# Booster_PA_OUT.net
KiCad netlist of a schematic drawn in Altium Designer
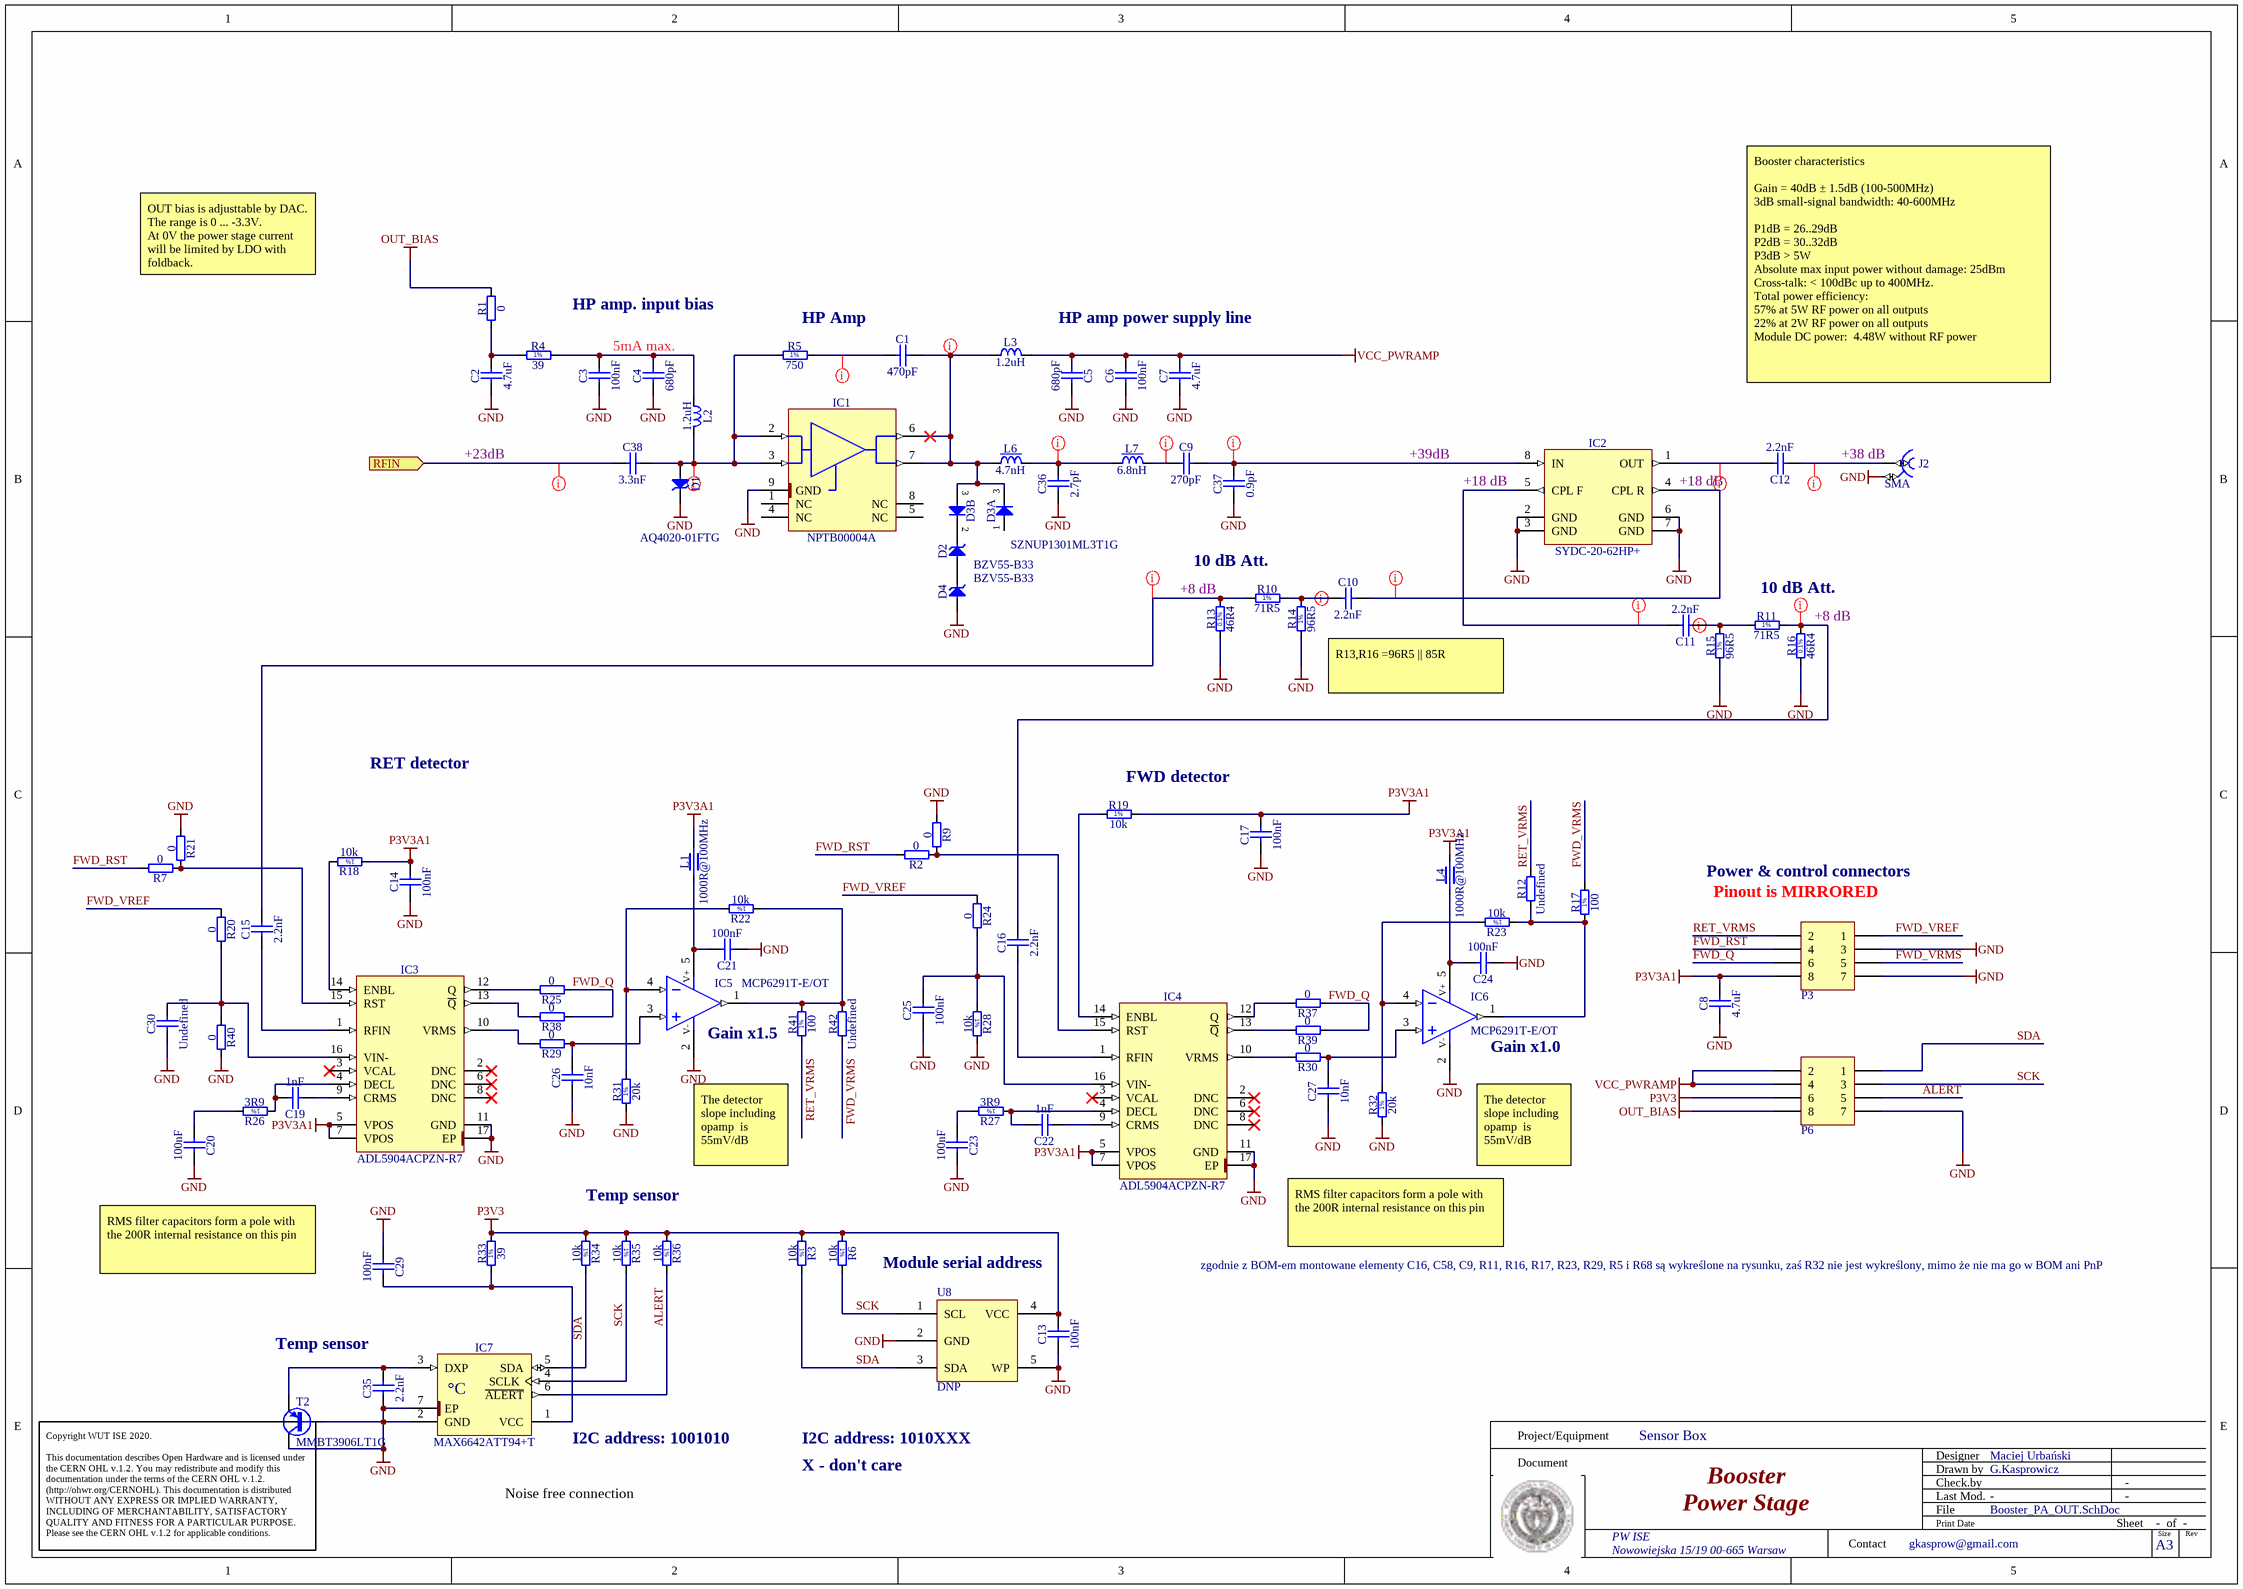
[diagram p0: Booster_PA_OUT.SchDoc]

(export (version "E")
  (design (tool "Eeschema 10.0.6"))
  (components
    (comp (ref "C1")
      (value "470pF")
      (footprint "CAPC1608X87N")
      (description "Non-polarised capacitor")
      (fields (field (name "PART NUMBER") "CC0603_470PF_50V_1%_NP0") (field (name "VOLTAGE") "50V"))
      (libsource (lib "Passives_RC") (part "CC0603_470PF_50V_1%_NP0"))
    )
    (comp (ref "C2")
      (value "4.7uF")
      (footprint "CAPC1709X95N")
      (description "Non-polarised capacitor")
      (fields
        (field (name "MANUFACTURER") "GENERIC")
        (field (name "MANUFACTURER PART NUMBER") "CC0603_4.7UF_16V_10%_X5R")
      )
      (libsource (lib "Capacitors") (part "Capacitor - non polarized"))
    )
    (comp (ref "C3")
      (value "100nF")
      (footprint "CAPC1005X55N")
      (description "Non-polarised capacitor")
      (fields
        (field (name "MANUFACTURER") "GENERIC")
        (field (name "MANUFACTURER PART NUMBER") "CC0402_100NF_50V_10%_X7R")
      )
      (libsource (lib "Capacitors") (part "Capacitor - non polarized"))
    )
    (comp (ref "C4")
      (value "680pF")
      (footprint "CAPC1608X87N")
      (description "Non-polarised capacitor")
      (fields
        (field (name "MANUFACTURER") "GENERIC")
        (field (name "MANUFACTURER PART NUMBER") "CC0603_680PF_50V_5%_NP0")
      )
      (libsource (lib "Capacitors") (part "Capacitor - non polarized"))
    )
    (comp (ref "C5")
      (value "680pF")
      (footprint "CAPC1608X87N")
      (description "Non-polarised capacitor")
      (fields
        (field (name "MANUFACTURER") "GENERIC")
        (field (name "MANUFACTURER PART NUMBER") "CC0603_680PF_50V_5%_NP0")
      )
      (libsource (lib "Capacitors") (part "Capacitor - non polarized"))
    )
    (comp (ref "C6")
      (value "100nF")
      (footprint "CAPC1005X55N")
      (description "Non-polarised capacitor")
      (fields
        (field (name "MANUFACTURER") "GENERIC")
        (field (name "MANUFACTURER PART NUMBER") "CC0402_100NF_50V_10%_X7R")
      )
      (libsource (lib "Capacitors") (part "Capacitor - non polarized"))
    )
    (comp (ref "C7")
      (value "4.7uF")
      (footprint "CAPC3225X270N")
      (description "Non-polarised capacitor")
      (fields (field (name "PART NUMBER") "CC1210_4.7UF_50V_10%_X7R") (field (name "VOLTAGE") "50V"))
      (libsource (lib "Capacitors") (part "Capacitor - non polarized"))
    )
    (comp (ref "C8")
      (value "4.7uF")
      (footprint "CAPC1709X95N")
      (description "Non-polarised capacitor")
      (fields
        (field (name "MANUFACTURER") "GENERIC")
        (field (name "MANUFACTURER PART NUMBER") "CC0603_4.7UF_16V_10%_X5R")
      )
      (libsource (lib "Capacitors") (part "Capacitor - non polarized"))
    )
    (comp (ref "C9")
      (value "270pF")
      (footprint "CAPC1608X87N")
      (description "Non-polarised capacitor")
      (fields (field (name "PART NUMBER") "CC0603_270PF_50V_1%_NP0") (field (name "VOLTAGE") "50V"))
      (libsource (lib "Passives_RC") (part "CC0603_270PF_50V_1%_NP0"))
    )
    (comp (ref "C10")
      (value "2.2nF")
      (footprint "CAPC1608X87N")
      (description "Non-polarised capacitor")
      (fields (field (name "PART NUMBER") "CC0603_2.2NF_50V_5%_C0G") (field (name "VOLTAGE") "50V"))
      (libsource (lib "Capacitors") (part "Capacitor - non polarized"))
    )
    (comp (ref "C11")
      (value "2.2nF")
      (footprint "CAPC1608X87N")
      (description "Non-polarised capacitor")
      (fields
        (field (name "MANUFACTURER") "GENERIC")
        (field (name "MANUFACTURER PART NUMBER") "CC0603_2.2NF_50V_5%_C0G")
      )
      (libsource (lib "Capacitors") (part "Capacitor - non polarized"))
    )
    (comp (ref "C12")
      (value "2.2nF")
      (footprint "CAPC1608X87N")
      (description "Non-polarised capacitor")
      (fields
        (field (name "MANUFACTURER") "GENERIC")
        (field (name "MANUFACTURER PART NUMBER") "CC0603_2.2NF_50V_5%_C0G")
      )
      (libsource (lib "Capacitors") (part "Capacitor - non polarized"))
    )
    (comp (ref "C13")
      (value "100nF")
      (footprint "CAPC1005X55N")
      (description "Non-polarised capacitor")
      (fields
        (field (name "MANUFACTURER") "GENERIC")
        (field (name "MANUFACTURER PART NUMBER") "CC0402_100NF_50V_10%_X7R")
      )
      (libsource (lib "Capacitors") (part "Capacitor - non polarized"))
    )
    (comp (ref "C14")
      (value "100nF")
      (footprint "CAPC1005X55N")
      (description "Non-polarised capacitor")
      (fields
        (field (name "MANUFACTURER") "GENERIC")
        (field (name "MANUFACTURER PART NUMBER") "CC0402_100NF_50V_10%_X7R")
      )
      (libsource (lib "Capacitors") (part "Capacitor - non polarized"))
    )
    (comp (ref "C15")
      (value "2.2nF")
      (footprint "CAPC1608X87N")
      (description "Non-polarised capacitor")
      (fields
        (field (name "MANUFACTURER") "GENERIC")
        (field (name "MANUFACTURER PART NUMBER") "CC0603_2.2NF_50V_5%_C0G")
      )
      (libsource (lib "Capacitors") (part "Capacitor - non polarized"))
    )
    (comp (ref "C16")
      (value "2.2nF")
      (footprint "CAPC1608X87N")
      (description "Non-polarised capacitor")
      (fields
        (field (name "MANUFACTURER") "GENERIC")
        (field (name "MANUFACTURER PART NUMBER") "CC0603_2.2NF_50V_5%_C0G")
      )
      (libsource (lib "Capacitors") (part "Capacitor - non polarized"))
    )
    (comp (ref "C17")
      (value "100nF")
      (footprint "CAPC1005X55N")
      (description "Non-polarised capacitor")
      (fields
        (field (name "MANUFACTURER") "GENERIC")
        (field (name "MANUFACTURER PART NUMBER") "CC0402_100NF_50V_10%_X7R")
      )
      (libsource (lib "Capacitors") (part "Capacitor - non polarized"))
    )
    (comp (ref "C19")
      (value "1nF")
      (footprint "CAPC1005X55N")
      (description "Non-polarised capacitor")
      (fields (field (name "PART NUMBER") "CC0402_1NF_50V_10%_X7R") (field (name "VOLTAGE") "50V"))
      (libsource (lib "Capacitors") (part "Capacitor - non polarized"))
    )
    (comp (ref "C20")
      (value "100nF")
      (footprint "CAPC1005X55N")
      (description "Non-polarised capacitor")
      (fields
        (field (name "MANUFACTURER") "GENERIC")
        (field (name "MANUFACTURER PART NUMBER") "CC0402_100NF_50V_10%_X7R")
      )
      (libsource (lib "Capacitors") (part "Capacitor - non polarized"))
    )
    (comp (ref "C21")
      (value "100nF")
      (footprint "CAPC1005X55N")
      (description "Non-polarised capacitor")
      (fields
        (field (name "MANUFACTURER") "GENERIC")
        (field (name "MANUFACTURER PART NUMBER") "CC0402_100NF_50V_10%_X7R")
      )
      (libsource (lib "Capacitors") (part "Capacitor - non polarized"))
    )
    (comp (ref "C22")
      (value "1nF")
      (footprint "CAPC1005X55N")
      (description "Non-polarised capacitor")
      (fields (field (name "PART NUMBER") "CC0402_1NF_50V_10%_X7R") (field (name "VOLTAGE") "50V"))
      (libsource (lib "Capacitors") (part "Capacitor - non polarized"))
    )
    (comp (ref "C23")
      (value "100nF")
      (footprint "CAPC1005X55N")
      (description "Non-polarised capacitor")
      (fields
        (field (name "MANUFACTURER") "GENERIC")
        (field (name "MANUFACTURER PART NUMBER") "CC0402_100NF_50V_10%_X7R")
      )
      (libsource (lib "Capacitors") (part "Capacitor - non polarized"))
    )
    (comp (ref "C24")
      (value "100nF")
      (footprint "CAPC1005X55N")
      (description "Non-polarised capacitor")
      (fields
        (field (name "MANUFACTURER") "GENERIC")
        (field (name "MANUFACTURER PART NUMBER") "CC0402_100NF_50V_10%_X7R")
      )
      (libsource (lib "Capacitors") (part "Capacitor - non polarized"))
    )
    (comp (ref "C25")
      (value "100nF")
      (footprint "CAPC1005X55N")
      (description "Non-polarised capacitor")
      (fields
        (field (name "MANUFACTURER") "GENERIC")
        (field (name "MANUFACTURER PART NUMBER") "CC0402_100NF_50V_10%_X7R")
      )
      (libsource (lib "Capacitors") (part "Capacitor - non polarized"))
    )
    (comp (ref "C26")
      (value "10nF")
      (footprint "CAPC1005X55N")
      (description "Non-polarised capacitor")
      (fields
        (field (name "MANUFACTURER") "GENERIC")
        (field (name "MANUFACTURER PART NUMBER") "CC0402_10NF_25V_10%_X7R")
      )
      (libsource (lib "Capacitors") (part "Capacitor - non polarized"))
    )
    (comp (ref "C27")
      (value "10nF")
      (footprint "CAPC1005X55N")
      (description "Non-polarised capacitor")
      (fields
        (field (name "MANUFACTURER") "GENERIC")
        (field (name "MANUFACTURER PART NUMBER") "CC0402_10NF_25V_10%_X7R")
      )
      (libsource (lib "Capacitors") (part "Capacitor - non polarized"))
    )
    (comp (ref "C29")
      (value "100nF")
      (footprint "CAPC1005X55N")
      (description "Non-polarised capacitor")
      (fields
        (field (name "MANUFACTURER") "GENERIC")
        (field (name "MANUFACTURER PART NUMBER") "CC0402_100NF_50V_10%_X7R")
      )
      (libsource (lib "Capacitors") (part "Capacitor - non polarized"))
    )
    (comp (ref "C30")
      (value "Undefined")
      (footprint "CAPC1608X90N")
      (description "Non-polarised capacitor")
      (fields (field (name "PART NUMBER") "CC0603_NO-VALUE"))
      (libsource (lib "Capacitors") (part "Capacitor - non polarized"))
    )
    (comp (ref "C35")
      (value "2.2nF")
      (footprint "CAPC1608X87N")
      (description "Non-polarised capacitor")
      (fields
        (field (name "MANUFACTURER") "GENERIC")
        (field (name "MANUFACTURER PART NUMBER") "CC0603_2.2NF_50V_5%_C0G")
      )
      (libsource (lib "Capacitors") (part "Capacitor - non polarized"))
    )
    (comp (ref "C36")
      (value "2.7pF")
      (footprint "CAPC1608X87N")
      (description "Non-polarised capacitor")
      (fields (field (name "PART NUMBER") "CC0603_2.7PF_50V_0.25PF_NP0") (field (name "VOLTAGE") "50V"))
      (libsource (lib "Capacitors") (part "Capacitor - non polarized"))
    )
    (comp (ref "C37")
      (value "0.9pF")
      (footprint "CAPC1608X87N")
      (description "Non-polarised capacitor")
      (fields (field (name "PART NUMBER") "CC0603_0.9PF_50V_0.05PF_NP0") (field (name "VOLTAGE") "50V"))
      (libsource (lib "Passives_RC") (part "CC0603_0.9PF_50V_0.05PF_NP0"))
    )
    (comp (ref "C38")
      (value "3.3nF")
      (footprint "CAPC1608X87N")
      (description "Non-polarised capacitor")
      (fields
        (field (name "MANUFACTURER") "GENERIC")
        (field (name "MANUFACTURER PART NUMBER") "CC0603_3.3NF_50V_5%_C0G")
      )
      (libsource (lib "Capacitors") (part "Capacitor - non polarized"))
    )
    (comp (ref "D1")
      (value "AQ4020-01FTG")
      (footprint "SOD2512X110N")
      (description "4V Transient Voltage Suppressor Diode (Uni-Directional)")
      (fields (field (name "VOLTAGE") "4V") (field (name "POWER") "735W"))
      (libsource (lib "Diodes") (part "D_TVS_AQ4020-01FTG"))
    )
    (comp (ref "D2")
      (value "BZV55-B33")
      (footprint "DIOMELF3515N")
      (description "Zener Diode")
      (fields (field (name "VOLTAGE") "33V") (field (name "POWER") "500mW"))
      (libsource (lib "ICs And Semiconductors") (part "Diode Zener"))
    )
    (comp (ref "D3")
      (value "SZNUP1301ML3T1G")
      (footprint "SOT95P240X110-3N")
      (description "Low Capacitance Diode Array for ESD Protection in a Single Data Line")
      (fields (field (name "VOLTAGE") "70V") (field (name "POWER") "215mA"))
      (libsource (lib "Diodes") (part "D_TVS_SZNUP1301ML3T1G"))
    )
    (comp (ref "D4")
      (value "BZV55-B33")
      (footprint "DIOMELF3515N")
      (description "Zener Diode")
      (fields (field (name "VOLTAGE") "33V") (field (name "POWER") "500mW"))
      (libsource (lib "ICs And Semiconductors") (part "Diode Zener"))
    )
    (comp (ref "IC1")
      (value "NPTB00004A")
      (footprint "SOIC127P610X167-9N-R245X335")
      (description "GaN Wideband Transistor 28V, 5W, DC - 6GHz")
      (fields (field (name "MANUFACTURER") "MACOM"))
      (libsource (lib "ICs And Semiconductors") (part "NPTB00004A"))
    )
    (comp (ref "IC2")
      (value "SYDC-20-62HP+")
      (footprint "MINI-CIRCUITS_AH202-1")
      (description "50Ohm, 10 to 540MHz, 25W, 20dB Bi-Directional Coupler")
      (fields (field (name "MANUFACTURER") "MINI-CIRCUITS"))
      (libsource (lib "ICs And Semiconductors") (part "SYDC-20-62HP+"))
    )
    (comp (ref "IC3")
      (value "ADL5904ACPZN-R7")
      (footprint "QFN50P300X300X80-17N-S175")
      (description "DC to 6 GHz, 45 dB TruPwr Detector With Envelope Threshold Detection")
      (fields (field (name "MANUFACTURER") "ANALOG DEVICES"))
      (libsource (lib "ICs And Semiconductors") (part "ADL5904"))
    )
    (comp (ref "IC4")
      (value "ADL5904ACPZN-R7")
      (footprint "QFN50P300X300X80-17N-S175")
      (description "DC to 6 GHz, 45 dB TruPwr Detector With Envelope Threshold Detection")
      (fields (field (name "MANUFACTURER") "ANALOG DEVICES"))
      (libsource (lib "ICs And Semiconductors") (part "ADL5904"))
    )
    (comp (ref "IC5")
      (value "MCP6291T-E/OT")
      (footprint "SOT95P270X145-5N")
      (description "Operational Amplifier")
      (fields (field (name "MANUFACTURER") "MICROCHIP TECHNOLOGY"))
      (libsource (lib "ICs And Semiconductors") (part "Operational Amplifier Type7"))
    )
    (comp (ref "IC6")
      (value "MCP6291T-E/OT")
      (footprint "SOT95P270X145-5N")
      (description "Operational Amplifier")
      (fields (field (name "MANUFACTURER") "MICROCHIP TECHNOLOGY"))
      (libsource (lib "ICs And Semiconductors") (part "Operational Amplifier Type7"))
    )
    (comp (ref "IC7")
      (value "MAX6642ATT94+T")
      (footprint "SON95P300X300X80-7N-R160X240")
      (description "±1°C, SMBus-Compatible Remote/Local Temperature Sensor with Overtemperature Alarm")
      (fields (field (name "MANUFACTURER") "MAXIM"))
      (libsource (lib "ICs And Semiconductors") (part "MAX6642ATT"))
    )
    (comp (ref "J2")
      (value "SMA")
      (footprint "MOLEX_73251-2120")
      (description "50 Ohm, SMA Edge Mount PCB, With Jam Nut And Lock Washer")
      (fields (field (name "PART NUMBER") "MOLEX_73251-2120") (field (name "MANUFACTURER") "MOLEX"))
      (libsource (lib "Connectors") (part "CON_SMA_RA_SMD_73251-2120"))
    )
    (comp (ref "L1")
      (value "1000R@100MHz")
      (footprint "INDC1608X95N")
      (fields
        (field (name "MANUFACTURER") "MURATA")
        (field (name "MANUFACTURER PART NUMBER") "BLM18HE102SN1")
        (field (name "PART NUMBER") "IND0603_MURATA_BLM18HE102SN1")
      )
      (libsource (lib "Inductors & Transformers") (part "Ferrite Bead"))
    )
    (comp (ref "L2")
      (value "1.2uH")
      (footprint "IND_TDK_ADL2012")
      (description "Inductor")
      (fields (field (name "PART NUMBER") "IND0805_TDK_ADL2012S-1R2M-T01") (field (name "POWER") "400mA"))
      (libsource (lib "Inductors_Transformers") (part "IND0805_TDK_ADL2012S-1R2M-T01"))
    )
    (comp (ref "L3")
      (value "1.2uH")
      (footprint "IND_TDK_ADL2012")
      (description "Inductor")
      (fields (field (name "PART NUMBER") "IND0805_TDK_ADL2012S-1R2M-T01") (field (name "POWER") "400mA"))
      (libsource (lib "") (part "IND0805_TDK_ADL2012S-1R2M-T01_1"))
    )
    (comp (ref "L4")
      (value "1000R@100MHz")
      (footprint "INDC1608X95N")
      (fields
        (field (name "MANUFACTURER") "MURATA")
        (field (name "MANUFACTURER PART NUMBER") "BLM18HE102SN1")
        (field (name "PART NUMBER") "IND0603_MURATA_BLM18HE102SN1")
      )
      (libsource (lib "Inductors & Transformers") (part "Ferrite Bead"))
    )
    (comp (ref "L6")
      (value "4.7nH")
      (footprint "IND_MURATA_LQW18AN_G8")
      (description "Inductor With Core")
      (fields
        (field (name "PART NUMBER") "IND0603_4.7NH_2%_MURATA_LQW18AN4N7G8Z")
        (field (name "POWER") "1.5A")
      )
      (libsource (lib "Inductors & Transformers") (part "Inductor With Magnetic core"))
    )
    (comp (ref "L7")
      (value "6.8nH")
      (footprint "IND_MURATA_LQW18AN_G8")
      (description "Inductor With Core")
      (fields
        (field (name "PART NUMBER") "IND0603_6.8NH_2%_MURATA_LQW18AN6N8G8Z")
        (field (name "POWER") "1.9A")
      )
      (libsource (lib "Inductors & Transformers") (part "Inductor With Magnetic core"))
    )
    (comp (ref "P3")
      (value "ZL264-8DG")
      (footprint "HDR2X4_SMD")
      (description "Header, 4-Pin, Dual Row")
      (libsource (lib "onyks") (part "HDR2X4"))
    )
    (comp (ref "P6")
      (value "ZL264-8DG")
      (footprint "HDR2X4_SMD")
      (description "Header, 4-Pin, Dual Row")
      (libsource (lib "onyks") (part "HDR2X4"))
    )
    (comp (ref "R1")
      (value "0")
      (footprint "RESC1005X40N")
      (description "Resistor")
      (fields
        (field (name "MANUFACTURER") "GENERIC")
        (field (name "MANUFACTURER PART NUMBER") "R0402_0R_JUMPER")
      )
      (libsource (lib "Resistors") (part "Resistor"))
    )
    (comp (ref "R2")
      (value "0")
      (footprint "RESC1005X40N")
      (description "Resistor")
      (fields
        (field (name "MANUFACTURER") "GENERIC")
        (field (name "MANUFACTURER PART NUMBER") "R0402_0R_JUMPER")
      )
      (libsource (lib "Resistors") (part "Resistor"))
    )
    (comp (ref "R3")
      (value "10k")
      (footprint "RESC1005X40N")
      (description "Resistor - 1%")
      (fields
        (field (name "MANUFACTURER") "GENERIC")
        (field (name "MANUFACTURER PART NUMBER") "R0402_10K_1%_0.0625W_100PPM")
      )
      (libsource (lib "Resistors") (part "Resistor - 1%"))
    )
    (comp (ref "R4")
      (value "39")
      (footprint "RESC1608X55N")
      (description "Resistor - 1%")
      (fields (field (name "PART NUMBER") "R0603_39R_1%_0.1W_100PPM") (field (name "POWER") "0.1W"))
      (libsource (lib "Resistors") (part "Resistor - 1%"))
    )
    (comp (ref "R5")
      (value "750")
      (footprint "RESC1608X55N")
      (description "Resistor - 1%")
      (fields (field (name "PART NUMBER") "R0603_750R_1%_0.1W_100PPM") (field (name "POWER") "0.1W"))
      (libsource (lib "Resistors") (part "Resistor - 1%"))
    )
    (comp (ref "R6")
      (value "10k")
      (footprint "RESC1005X40N")
      (description "Resistor - 1%")
      (fields
        (field (name "MANUFACTURER") "GENERIC")
        (field (name "MANUFACTURER PART NUMBER") "R0402_10K_1%_0.0625W_100PPM")
      )
      (libsource (lib "Resistors") (part "Resistor - 1%"))
    )
    (comp (ref "R7")
      (value "0")
      (footprint "RESC1005X40N")
      (description "Resistor")
      (fields
        (field (name "MANUFACTURER") "GENERIC")
        (field (name "MANUFACTURER PART NUMBER") "R0402_0R_JUMPER")
      )
      (libsource (lib "Resistors") (part "Resistor"))
    )
    (comp (ref "R9")
      (value "0")
      (footprint "RESC1005X40N")
      (description "Resistor")
      (fields
        (field (name "MANUFACTURER") "GENERIC")
        (field (name "MANUFACTURER PART NUMBER") "R0402_0R_JUMPER")
      )
      (libsource (lib "Resistors") (part "Resistor"))
    )
    (comp (ref "R10")
      (value "71R5")
      (footprint "RESC1608X55N")
      (description "Resistor - 1%")
      (fields (field (name "PART NUMBER") "R0603_71R5_1%_0.1W_100PPM") (field (name "POWER") "0.1W"))
      (libsource (lib "Resistors") (part "Resistor - 1%"))
    )
    (comp (ref "R11")
      (value "71R5")
      (footprint "RESC1608X55N")
      (description "Resistor - 1%")
      (fields (field (name "PART NUMBER") "R0603_71R5_1%_0.1W_100PPM") (field (name "POWER") "0.1W"))
      (libsource (lib "Resistors") (part "Resistor - 1%"))
    )
    (comp (ref "R12")
      (value "Undefined")
      (footprint "RESC1608X55N")
      (description "Resistor")
      (fields (field (name "MANUFACTURER PART NUMBER") "R0603_NO-VALUE"))
      (libsource (lib "Resistors") (part "Resistor"))
    )
    (comp (ref "R13")
      (value "46R4")
      (footprint "RESC1608X55N")
      (description "Resistor - 0.1%")
      (fields (field (name "PART NUMBER") "R0603_46R4_0.1%_0.063W_10PPM") (field (name "POWER") "0.063W"))
      (libsource (lib "Resistors") (part "Resistor - 0.1%"))
    )
    (comp (ref "R14")
      (value "96R5")
      (footprint "RESC1608X55N")
      (description "Resistor - 0.5%")
      (fields (field (name "PART NUMBER") "R0603_96R5_0.5%_0.1W_50PPM") (field (name "POWER") "0.1W"))
      (libsource (lib "Passives_RC") (part "R0603_96R5_0.5%_0.1W_50PPM"))
    )
    (comp (ref "R15")
      (value "96R5")
      (footprint "RESC1608X55N")
      (description "Resistor - 0.5%")
      (fields (field (name "PART NUMBER") "R0603_96R5_0.5%_0.1W_50PPM") (field (name "POWER") "0.1W"))
      (libsource (lib "Passives_RC") (part "R0603_96R5_0.5%_0.1W_50PPM"))
    )
    (comp (ref "R16")
      (value "46R4")
      (footprint "RESC1608X55N")
      (description "Resistor - 0.1%")
      (fields (field (name "PART NUMBER") "R0603_46R4_0.1%_0.063W_10PPM") (field (name "POWER") "0.063W"))
      (libsource (lib "Resistors") (part "Resistor - 0.1%"))
    )
    (comp (ref "R17")
      (value "100")
      (footprint "RESC1608X55N")
      (description "Resistor - 1%")
      (fields
        (field (name "MANUFACTURER") "GENERIC")
        (field (name "MANUFACTURER PART NUMBER") "R0603_100R_1%_0.1W_100PPM")
      )
      (libsource (lib "Resistors") (part "Resistor - 1%"))
    )
    (comp (ref "R18")
      (value "10k")
      (footprint "RESC1005X40N")
      (description "Resistor - 1%")
      (fields
        (field (name "MANUFACTURER") "GENERIC")
        (field (name "MANUFACTURER PART NUMBER") "R0402_10K_1%_0.0625W_100PPM")
      )
      (libsource (lib "Resistors") (part "Resistor - 1%"))
    )
    (comp (ref "R19")
      (value "10k")
      (footprint "RESC1005X40N")
      (description "Resistor - 1%")
      (fields (field (name "PART NUMBER") "R0402_10K_1%_0.0625W_100PPM") (field (name "POWER") "0.0625W"))
      (libsource (lib "Resistors") (part "Resistor - 1%"))
    )
    (comp (ref "R20")
      (value "0")
      (footprint "RESC1005X40N")
      (description "Resistor")
      (fields
        (field (name "MANUFACTURER") "GENERIC")
        (field (name "MANUFACTURER PART NUMBER") "R0402_0R_JUMPER")
      )
      (libsource (lib "Resistors") (part "Resistor"))
    )
    (comp (ref "R21")
      (value "0")
      (footprint "RESC1005X40N")
      (description "Resistor")
      (fields
        (field (name "MANUFACTURER") "GENERIC")
        (field (name "MANUFACTURER PART NUMBER") "R0402_0R_JUMPER")
      )
      (libsource (lib "Resistors") (part "Resistor"))
    )
    (comp (ref "R22")
      (value "10k")
      (footprint "RESC1005X40N")
      (description "Resistor - 1%")
      (fields
        (field (name "MANUFACTURER") "GENERIC")
        (field (name "MANUFACTURER PART NUMBER") "R0402_10K_1%_0.0625W_100PPM")
      )
      (libsource (lib "Resistors") (part "Resistor - 1%"))
    )
    (comp (ref "R23")
      (value "10k")
      (footprint "RESC1005X40N")
      (description "Resistor - 1%")
      (fields
        (field (name "MANUFACTURER") "GENERIC")
        (field (name "MANUFACTURER PART NUMBER") "R0402_10K_1%_0.0625W_100PPM")
      )
      (libsource (lib "Resistors") (part "Resistor - 1%"))
    )
    (comp (ref "R24")
      (value "0")
      (footprint "RESC1005X40N")
      (description "Resistor")
      (fields
        (field (name "MANUFACTURER") "GENERIC")
        (field (name "MANUFACTURER PART NUMBER") "R0402_0R_JUMPER")
      )
      (libsource (lib "Resistors") (part "Resistor"))
    )
    (comp (ref "R25")
      (value "0")
      (footprint "RESC1005X40N")
      (description "Resistor")
      (fields
        (field (name "MANUFACTURER") "GENERIC")
        (field (name "MANUFACTURER PART NUMBER") "R0402_0R_JUMPER")
      )
      (libsource (lib "Resistors") (part "Resistor"))
    )
    (comp (ref "R26")
      (value "3R9")
      (footprint "RESC1005X40N")
      (description "Resistor - 1%")
      (fields (field (name "PART NUMBER") "R0402_3R9_1%_0.0625W_200PPM") (field (name "POWER") "0.0625W"))
      (libsource (lib "Resistors") (part "Resistor - 1%"))
    )
    (comp (ref "R27")
      (value "3R9")
      (footprint "RESC1005X40N")
      (description "Resistor - 1%")
      (fields (field (name "PART NUMBER") "R0402_3R9_1%_0.0625W_200PPM") (field (name "POWER") "0.0625W"))
      (libsource (lib "Resistors") (part "Resistor - 1%"))
    )
    (comp (ref "R28")
      (value "10k")
      (footprint "RESC1005X40N")
      (description "Resistor - 1%")
      (fields
        (field (name "MANUFACTURER") "GENERIC")
        (field (name "MANUFACTURER PART NUMBER") "R0402_10K_1%_0.0625W_100PPM")
      )
      (libsource (lib "Resistors") (part "Resistor - 1%"))
    )
    (comp (ref "R29")
      (value "0")
      (footprint "RESC1005X40N")
      (description "Resistor")
      (fields
        (field (name "MANUFACTURER") "GENERIC")
        (field (name "MANUFACTURER PART NUMBER") "R0402_0R_JUMPER")
      )
      (libsource (lib "Resistors") (part "Resistor"))
    )
    (comp (ref "R30")
      (value "0")
      (footprint "RESC1005X40N")
      (description "Resistor")
      (fields
        (field (name "MANUFACTURER") "GENERIC")
        (field (name "MANUFACTURER PART NUMBER") "R0402_0R_JUMPER")
      )
      (libsource (lib "Resistors") (part "Resistor"))
    )
    (comp (ref "R31")
      (value "20k")
      (footprint "RESC1608X55N")
      (description "Resistor - 1%")
      (fields (field (name "PART NUMBER") "R0603_20K_1%_0.1W_100PPM") (field (name "POWER") "0.1W"))
      (libsource (lib "Resistors") (part "Resistor - 1%"))
    )
    (comp (ref "R32")
      (value "20k")
      (footprint "RESC1608X55N")
      (description "Resistor - 1%")
      (fields (field (name "PART NUMBER") "R0603_20K_1%_0.1W_100PPM") (field (name "POWER") "0.1W"))
      (libsource (lib "Resistors") (part "Resistor - 1%"))
    )
    (comp (ref "R33")
      (value "39")
      (footprint "RESC1608X55N")
      (description "Resistor - 1%")
      (fields (field (name "PART NUMBER") "R0603_39R_1%_0.1W_100PPM") (field (name "POWER") "0.1W"))
      (libsource (lib "Resistors") (part "Resistor - 1%"))
    )
    (comp (ref "R34")
      (value "10k")
      (footprint "RESC1005X40N")
      (description "Resistor - 1%")
      (fields
        (field (name "MANUFACTURER") "GENERIC")
        (field (name "MANUFACTURER PART NUMBER") "R0402_10K_1%_0.0625W_100PPM")
      )
      (libsource (lib "Resistors") (part "Resistor - 1%"))
    )
    (comp (ref "R35")
      (value "10k")
      (footprint "RESC1005X40N")
      (description "Resistor - 1%")
      (fields
        (field (name "MANUFACTURER") "GENERIC")
        (field (name "MANUFACTURER PART NUMBER") "R0402_10K_1%_0.0625W_100PPM")
      )
      (libsource (lib "Resistors") (part "Resistor - 1%"))
    )
    (comp (ref "R36")
      (value "10k")
      (footprint "RESC1005X40N")
      (description "Resistor - 1%")
      (fields
        (field (name "MANUFACTURER") "GENERIC")
        (field (name "MANUFACTURER PART NUMBER") "R0402_10K_1%_0.0625W_100PPM")
      )
      (libsource (lib "Resistors") (part "Resistor - 1%"))
    )
    (comp (ref "R37")
      (value "0")
      (footprint "RESC1005X40N")
      (description "Resistor")
      (fields
        (field (name "MANUFACTURER") "GENERIC")
        (field (name "MANUFACTURER PART NUMBER") "R0402_0R_JUMPER")
      )
      (libsource (lib "Resistors") (part "Resistor"))
    )
    (comp (ref "R38")
      (value "0")
      (footprint "RESC1005X40N")
      (description "Resistor")
      (fields
        (field (name "MANUFACTURER") "GENERIC")
        (field (name "MANUFACTURER PART NUMBER") "R0402_0R_JUMPER")
      )
      (libsource (lib "Resistors") (part "Resistor"))
    )
    (comp (ref "R39")
      (value "0")
      (footprint "RESC1005X40N")
      (description "Resistor")
      (fields
        (field (name "MANUFACTURER") "GENERIC")
        (field (name "MANUFACTURER PART NUMBER") "R0402_0R_JUMPER")
      )
      (libsource (lib "Resistors") (part "Resistor"))
    )
    (comp (ref "R40")
      (value "0")
      (footprint "RESC1005X40N")
      (description "Resistor")
      (fields
        (field (name "MANUFACTURER") "GENERIC")
        (field (name "MANUFACTURER PART NUMBER") "R0402_0R_JUMPER")
      )
      (libsource (lib "Resistors") (part "Resistor"))
    )
    (comp (ref "R41")
      (value "100")
      (footprint "RESC1608X55N")
      (description "Resistor - 1%")
      (fields
        (field (name "MANUFACTURER") "GENERIC")
        (field (name "MANUFACTURER PART NUMBER") "R0603_100R_1%_0.1W_100PPM")
      )
      (libsource (lib "Resistors") (part "Resistor - 1%"))
    )
    (comp (ref "R42")
      (value "Undefined")
      (footprint "RESC1608X55N")
      (description "Resistor")
      (fields (field (name "MANUFACTURER PART NUMBER") "R0603_NO-VALUE"))
      (libsource (lib "Resistors") (part "Resistor"))
    )
    (comp (ref "T2")
      (value "MMBT3906LT1G")
      (footprint "SOT95P240X110-3N")
      (description "PNP Transistor")
      (fields (field (name "MANUFACTURER") "ON SEMICONDUCTOR"))
      (libsource (lib "ICs And Semiconductors") (part "PNP B1 E2 C3"))
    )
    (comp (ref "U8")
      (value "DNP")
      (footprint "SOT23-5_N")
      (description "1K I2  C™ Serial EEPROM with Half-Array Write-Protect")
      (fields (field (name "MANUFACTURER") "Microchip"))
      (libsource (lib "uklady_cyfrowe") (part "24AA01H"))
    )
  )
  (nets
    (net (code "1") (name "/ALERT") (class "Default")
      (node (ref "IC7") (pin "6") (pinfunction "~{ALERT}_6") (pintype "output"))
      (node (ref "P6") (pin "5") (pinfunction "5_5") (pintype "passive"))
      (node (ref "R36") (pin "2") (pinfunction "2_2") (pintype "passive"))
    )
    (net (code "2") (name "/FWD_Q") (class "Default")
      (node (ref "P3") (pin "6") (pinfunction "6_6") (pintype "passive"))
      (node (ref "R25") (pin "1") (pinfunction "1_1") (pintype "passive"))
      (node (ref "R37") (pin "1") (pinfunction "1_1") (pintype "passive"))
      (node (ref "R38") (pin "1") (pinfunction "1_1") (pintype "passive"))
      (node (ref "R39") (pin "1") (pinfunction "1_1") (pintype "passive"))
    )
    (net (code "3") (name "/FWD_RST") (class "Default")
      (node (ref "P3") (pin "4") (pinfunction "4_4") (pintype "passive"))
      (node (ref "R2") (pin "2") (pinfunction "2_2") (pintype "passive"))
      (node (ref "R7") (pin "2") (pinfunction "2_2") (pintype "passive"))
    )
    (net (code "4") (name "/FWD_VREF") (class "Default")
      (node (ref "P3") (pin "1") (pinfunction "1_1") (pintype "passive"))
      (node (ref "R20") (pin "1") (pinfunction "1_1") (pintype "passive"))
      (node (ref "R24") (pin "1") (pinfunction "1_1") (pintype "passive"))
    )
    (net (code "5") (name "/FWD_VRMS") (class "Default")
      (node (ref "P3") (pin "5") (pinfunction "5_5") (pintype "passive"))
      (node (ref "R17") (pin "2") (pinfunction "2_2") (pintype "passive"))
      (node (ref "R42") (pin "1") (pinfunction "1_1") (pintype "passive"))
    )
    (net (code "6") (name "/RET_VRMS") (class "Default")
      (node (ref "P3") (pin "2") (pinfunction "2_2") (pintype "passive"))
      (node (ref "R12") (pin "2") (pinfunction "2_2") (pintype "passive"))
      (node (ref "R41") (pin "1") (pinfunction "1_1") (pintype "passive"))
    )
    (net (code "7") (name "/RFIN") (class "Default")
      (node (ref "C38") (pin "2") (pinfunction "2_2") (pintype "passive"))
    )
    (net (code "8") (name "/SCK") (class "Default")
      (node (ref "IC7") (pin "4") (pinfunction "SCLK_4") (pintype "input"))
      (node (ref "P6") (pin "3") (pinfunction "3_3") (pintype "passive"))
      (node (ref "R35") (pin "2") (pinfunction "2_2") (pintype "passive"))
      (node (ref "R6") (pin "2") (pinfunction "2_2") (pintype "passive"))
      (node (ref "U8") (pin "1") (pinfunction "SCL_1") (pintype "passive"))
    )
    (net (code "9") (name "/SDA") (class "Default")
      (node (ref "IC7") (pin "5") (pinfunction "SDA_5") (pintype "bidirectional"))
      (node (ref "P6") (pin "1") (pinfunction "1_1") (pintype "passive"))
      (node (ref "R3") (pin "2") (pinfunction "2_2") (pintype "passive"))
      (node (ref "R34") (pin "2") (pinfunction "2_2") (pintype "passive"))
      (node (ref "U8") (pin "3") (pinfunction "SDA_3") (pintype "passive"))
    )
    (net (code "10") (name "GND") (class "Default")
      (node (ref "C13") (pin "1") (pinfunction "1_1") (pintype "passive"))
      (node (ref "C14") (pin "1") (pinfunction "1_1") (pintype "passive"))
      (node (ref "C17") (pin "1") (pinfunction "1_1") (pintype "passive"))
      (node (ref "C2") (pin "1") (pinfunction "1_1") (pintype "passive"))
      (node (ref "C20") (pin "2") (pinfunction "2_2") (pintype "passive"))
      (node (ref "C21") (pin "1") (pinfunction "1_1") (pintype "passive"))
      (node (ref "C23") (pin "2") (pinfunction "2_2") (pintype "passive"))
      (node (ref "C24") (pin "1") (pinfunction "1_1") (pintype "passive"))
      (node (ref "C25") (pin "1") (pinfunction "1_1") (pintype "passive"))
      (node (ref "C26") (pin "1") (pinfunction "1_1") (pintype "passive"))
      (node (ref "C27") (pin "1") (pinfunction "1_1") (pintype "passive"))
      (node (ref "C29") (pin "1") (pinfunction "1_1") (pintype "passive"))
      (node (ref "C3") (pin "1") (pinfunction "1_1") (pintype "passive"))
      (node (ref "C30") (pin "1") (pinfunction "1_1") (pintype "passive"))
      (node (ref "C35") (pin "1") (pinfunction "1_1") (pintype "passive"))
      (node (ref "C36") (pin "1") (pinfunction "1_1") (pintype "passive"))
      (node (ref "C37") (pin "1") (pinfunction "1_1") (pintype "passive"))
      (node (ref "C4") (pin "1") (pinfunction "1_1") (pintype "passive"))
      (node (ref "C5") (pin "1") (pinfunction "1_1") (pintype "passive"))
      (node (ref "C6") (pin "1") (pinfunction "1_1") (pintype "passive"))
      (node (ref "C7") (pin "1") (pinfunction "1_1") (pintype "passive"))
      (node (ref "C8") (pin "1") (pinfunction "1_1") (pintype "passive"))
      (node (ref "D1") (pin "1") (pinfunction "C_1") (pintype "passive"))
      (node (ref "D4") (pin "2") (pinfunction "A_2") (pintype "passive"))
      (node (ref "IC1") (pin "9") (pinfunction "GND_9") (pintype "power_in"))
      (node (ref "IC2") (pin "2") (pinfunction "GND_2") (pintype "power_in"))
      (node (ref "IC2") (pin "3") (pinfunction "GND_3") (pintype "power_in"))
      (node (ref "IC2") (pin "6") (pinfunction "GND_6") (pintype "power_in"))
      (node (ref "IC2") (pin "7") (pinfunction "GND_7") (pintype "power_in"))
      (node (ref "IC3") (pin "11") (pinfunction "GND_11") (pintype "power_in"))
      (node (ref "IC3") (pin "17") (pinfunction "EP_17") (pintype "power_in"))
      (node (ref "IC4") (pin "11") (pinfunction "GND_11") (pintype "power_in"))
      (node (ref "IC4") (pin "17") (pinfunction "EP_17") (pintype "power_in"))
      (node (ref "IC5") (pin "2") (pinfunction "V-_2") (pintype "power_in"))
      (node (ref "IC6") (pin "2") (pinfunction "V-_2") (pintype "power_in"))
      (node (ref "IC7") (pin "2") (pinfunction "GND_2") (pintype "power_in"))
      (node (ref "IC7") (pin "7") (pinfunction "EP_7") (pintype "power_in"))
      (node (ref "J2") (pin "2") (pinfunction "2_2") (pintype "bidirectional"))
      (node (ref "P3") (pin "3") (pinfunction "3_3") (pintype "passive"))
      (node (ref "P3") (pin "7") (pinfunction "7_7") (pintype "passive"))
      (node (ref "P6") (pin "7") (pinfunction "7_7") (pintype "passive"))
      (node (ref "R13") (pin "1") (pinfunction "1_1") (pintype "passive"))
      (node (ref "R14") (pin "1") (pinfunction "1_1") (pintype "passive"))
      (node (ref "R15") (pin "1") (pinfunction "1_1") (pintype "passive"))
      (node (ref "R16") (pin "1") (pinfunction "1_1") (pintype "passive"))
      (node (ref "R21") (pin "1") (pinfunction "1_1") (pintype "passive"))
      (node (ref "R28") (pin "2") (pinfunction "2_2") (pintype "passive"))
      (node (ref "R31") (pin "1") (pinfunction "1_1") (pintype "passive"))
      (node (ref "R32") (pin "1") (pinfunction "1_1") (pintype "passive"))
      (node (ref "R40") (pin "2") (pinfunction "2_2") (pintype "passive"))
      (node (ref "R9") (pin "1") (pinfunction "1_1") (pintype "passive"))
      (node (ref "T2") (pin "1") (pinfunction "B_1") (pintype "passive"))
      (node (ref "T2") (pin "3") (pinfunction "C_3") (pintype "passive"))
      (node (ref "U8") (pin "2") (pinfunction "GND_2") (pintype "passive"))
      (node (ref "U8") (pin "5") (pinfunction "WP_5") (pintype "passive"))
    )
    (net (code "11") (name "Net-(C1-Pad1)") (class "Default")
      (node (ref "C1") (pin "1") (pinfunction "1_1") (pintype "passive"))
      (node (ref "R5") (pin "2") (pinfunction "2_2") (pintype "passive"))
    )
    (net (code "12") (name "Net-(C2-Pad2)") (class "Default")
      (node (ref "C2") (pin "2") (pinfunction "2_2") (pintype "passive"))
      (node (ref "R1") (pin "1") (pinfunction "1_1") (pintype "passive"))
      (node (ref "R4") (pin "1") (pinfunction "1_1") (pintype "passive"))
    )
    (net (code "13") (name "Net-(C3-Pad2)") (class "Default")
      (node (ref "C3") (pin "2") (pinfunction "2_2") (pintype "passive"))
      (node (ref "C4") (pin "2") (pinfunction "2_2") (pintype "passive"))
      (node (ref "L2") (pin "1") (pinfunction "1_1") (pintype "passive"))
      (node (ref "R4") (pin "2") (pinfunction "2_2") (pintype "passive"))
    )
    (net (code "14") (name "Net-(C9-Pad1)") (class "Default")
      (node (ref "C9") (pin "1") (pinfunction "1_1") (pintype "passive"))
      (node (ref "L7") (pin "2") (pinfunction "2_2") (pintype "passive"))
    )
    (net (code "15") (name "Net-(C10-Pad1)") (class "Default")
      (node (ref "C10") (pin "1") (pinfunction "1_1") (pintype "passive"))
      (node (ref "R10") (pin "2") (pinfunction "2_2") (pintype "passive"))
      (node (ref "R14") (pin "2") (pinfunction "2_2") (pintype "passive"))
    )
    (net (code "16") (name "Net-(C11-Pad1)") (class "Default")
      (node (ref "C11") (pin "1") (pinfunction "1_1") (pintype "passive"))
      (node (ref "R11") (pin "1") (pinfunction "1_1") (pintype "passive"))
      (node (ref "R15") (pin "2") (pinfunction "2_2") (pintype "passive"))
    )
    (net (code "17") (name "Net-(C12-Pad1)") (class "Default")
      (node (ref "C12") (pin "1") (pinfunction "1_1") (pintype "passive"))
      (node (ref "J2") (pin "1") (pinfunction "1_1") (pintype "bidirectional"))
    )
    (net (code "18") (name "Net-(C15-Pad2)") (class "Default")
      (node (ref "C15") (pin "2") (pinfunction "2_2") (pintype "passive"))
      (node (ref "R10") (pin "1") (pinfunction "1_1") (pintype "passive"))
      (node (ref "R13") (pin "2") (pinfunction "2_2") (pintype "passive"))
    )
    (net (code "19") (name "Net-(C16-Pad2)") (class "Default")
      (node (ref "C16") (pin "2") (pinfunction "2_2") (pintype "passive"))
      (node (ref "R11") (pin "2") (pinfunction "2_2") (pintype "passive"))
      (node (ref "R16") (pin "2") (pinfunction "2_2") (pintype "passive"))
    )
    (net (code "20") (name "Net-(C20-Pad1)") (class "Default")
      (node (ref "C20") (pin "1") (pinfunction "1_1") (pintype "passive"))
      (node (ref "R26") (pin "2") (pinfunction "2_2") (pintype "passive"))
    )
    (net (code "21") (name "Net-(C23-Pad1)") (class "Default")
      (node (ref "C23") (pin "1") (pinfunction "1_1") (pintype "passive"))
      (node (ref "R27") (pin "2") (pinfunction "2_2") (pintype "passive"))
    )
    (net (code "22") (name "Net-(C36-Pad2)") (class "Default")
      (node (ref "C36") (pin "2") (pinfunction "2_2") (pintype "passive"))
      (node (ref "L6") (pin "2") (pinfunction "2_2") (pintype "passive"))
      (node (ref "L7") (pin "1") (pinfunction "1_1") (pintype "passive"))
    )
    (net (code "23") (name "Net-(D1-A)") (class "Default")
      (node (ref "C38") (pin "1") (pinfunction "1_1") (pintype "passive"))
      (node (ref "D1") (pin "2") (pinfunction "A_2") (pintype "passive"))
      (node (ref "IC1") (pin "2") (pinfunction "RF_IN_2") (pintype "input"))
      (node (ref "IC1") (pin "3") (pinfunction "RF_IN_3") (pintype "input"))
      (node (ref "L2") (pin "2") (pinfunction "2_2") (pintype "passive"))
      (node (ref "R5") (pin "1") (pinfunction "1_1") (pintype "passive"))
    )
    (net (code "24") (name "Net-(D2-A)") (class "Default")
      (node (ref "D2") (pin "2") (pinfunction "A_2") (pintype "passive"))
      (node (ref "D4") (pin "1") (pinfunction "C_1") (pintype "passive"))
    )
    (net (code "25") (name "Net-(D2-C)") (class "Default")
      (node (ref "D2") (pin "1") (pinfunction "C_1") (pintype "passive"))
      (node (ref "D3") (pin "2") (pinfunction "C_2") (pintype "passive"))
    )
    (net (code "26") (name "Net-(D3A-COMAC)") (class "Default")
      (node (ref "C1") (pin "2") (pinfunction "2_2") (pintype "passive"))
      (node (ref "D3") (pin "3") (pinfunction "COMAC_3") (pintype "passive"))
      (node (ref "IC1") (pin "6") (pinfunction "RF_OUT_6") (pintype "output"))
      (node (ref "IC1") (pin "7") (pinfunction "RF_OUT_7") (pintype "output"))
      (node (ref "L3") (pin "1") (pinfunction "1_1") (pintype "passive"))
      (node (ref "L6") (pin "1") (pinfunction "1_1") (pintype "passive"))
    )
    (net (code "27") (name "Net-(IC2-CPL_F)") (class "Default")
      (node (ref "C11") (pin "2") (pinfunction "2_2") (pintype "passive"))
      (node (ref "IC2") (pin "5") (pinfunction "CPL_F_5") (pintype "output"))
    )
    (net (code "28") (name "Net-(IC2-CPL_R)") (class "Default")
      (node (ref "C10") (pin "2") (pinfunction "2_2") (pintype "passive"))
      (node (ref "IC2") (pin "4") (pinfunction "CPL_R_4") (pintype "output"))
    )
    (net (code "29") (name "Net-(IC2-IN)") (class "Default")
      (node (ref "C37") (pin "2") (pinfunction "2_2") (pintype "passive"))
      (node (ref "C9") (pin "2") (pinfunction "2_2") (pintype "passive"))
      (node (ref "IC2") (pin "8") (pinfunction "IN_8") (pintype "input"))
    )
    (net (code "30") (name "Net-(IC2-OUT)") (class "Default")
      (node (ref "C12") (pin "2") (pinfunction "2_2") (pintype "passive"))
      (node (ref "IC2") (pin "1") (pinfunction "OUT_1") (pintype "output"))
    )
    (net (code "31") (name "Net-(IC3-CRMS)") (class "Default")
      (node (ref "C19") (pin "1") (pinfunction "1_1") (pintype "passive"))
      (node (ref "IC3") (pin "9") (pinfunction "CRMS_9") (pintype "input"))
    )
    (net (code "32") (name "Net-(IC3-DECL)") (class "Default")
      (node (ref "C19") (pin "2") (pinfunction "2_2") (pintype "passive"))
      (node (ref "IC3") (pin "4") (pinfunction "DECL_4") (pintype "input"))
      (node (ref "R26") (pin "1") (pinfunction "1_1") (pintype "passive"))
    )
    (net (code "33") (name "Net-(IC3-ENBL)") (class "Default")
      (node (ref "IC3") (pin "14") (pinfunction "ENBL_14") (pintype "input"))
      (node (ref "R18") (pin "2") (pinfunction "2_2") (pintype "passive"))
    )
    (net (code "34") (name "Net-(IC3-Q)") (class "Default")
      (node (ref "IC3") (pin "12") (pinfunction "Q_12") (pintype "output"))
      (node (ref "R25") (pin "2") (pinfunction "2_2") (pintype "passive"))
    )
    (net (code "35") (name "Net-(IC3-RFIN)") (class "Default")
      (node (ref "C15") (pin "1") (pinfunction "1_1") (pintype "passive"))
      (node (ref "IC3") (pin "1") (pinfunction "RFIN_1") (pintype "input"))
    )
    (net (code "36") (name "Net-(IC3-RST)") (class "Default")
      (node (ref "IC3") (pin "15") (pinfunction "RST_15") (pintype "input"))
      (node (ref "R21") (pin "2") (pinfunction "2_2") (pintype "passive"))
      (node (ref "R7") (pin "1") (pinfunction "1_1") (pintype "passive"))
    )
    (net (code "37") (name "Net-(IC3-VIN-)") (class "Default")
      (node (ref "C30") (pin "2") (pinfunction "2_2") (pintype "passive"))
      (node (ref "IC3") (pin "16") (pinfunction "VIN-_16") (pintype "input"))
      (node (ref "R20") (pin "2") (pinfunction "2_2") (pintype "passive"))
      (node (ref "R40") (pin "1") (pinfunction "1_1") (pintype "passive"))
    )
    (net (code "38") (name "Net-(IC3-VRMS)") (class "Default")
      (node (ref "IC3") (pin "10") (pinfunction "VRMS_10") (pintype "output"))
      (node (ref "R29") (pin "2") (pinfunction "2_2") (pintype "passive"))
    )
    (net (code "39") (name "Net-(IC3-~{Q})") (class "Default")
      (node (ref "IC3") (pin "13") (pinfunction "~{Q}_13") (pintype "output"))
      (node (ref "R38") (pin "2") (pinfunction "2_2") (pintype "passive"))
    )
    (net (code "40") (name "Net-(IC4-CRMS)") (class "Default")
      (node (ref "C22") (pin "1") (pinfunction "1_1") (pintype "passive"))
      (node (ref "IC4") (pin "9") (pinfunction "CRMS_9") (pintype "input"))
    )
    (net (code "41") (name "Net-(IC4-DECL)") (class "Default")
      (node (ref "C22") (pin "2") (pinfunction "2_2") (pintype "passive"))
      (node (ref "IC4") (pin "4") (pinfunction "DECL_4") (pintype "input"))
      (node (ref "R27") (pin "1") (pinfunction "1_1") (pintype "passive"))
    )
    (net (code "42") (name "Net-(IC4-ENBL)") (class "Default")
      (node (ref "IC4") (pin "14") (pinfunction "ENBL_14") (pintype "input"))
      (node (ref "R19") (pin "1") (pinfunction "1_1") (pintype "passive"))
    )
    (net (code "43") (name "Net-(IC4-Q)") (class "Default")
      (node (ref "IC4") (pin "12") (pinfunction "Q_12") (pintype "output"))
      (node (ref "R37") (pin "2") (pinfunction "2_2") (pintype "passive"))
    )
    (net (code "44") (name "Net-(IC4-RFIN)") (class "Default")
      (node (ref "C16") (pin "1") (pinfunction "1_1") (pintype "passive"))
      (node (ref "IC4") (pin "1") (pinfunction "RFIN_1") (pintype "input"))
    )
    (net (code "45") (name "Net-(IC4-RST)") (class "Default")
      (node (ref "IC4") (pin "15") (pinfunction "RST_15") (pintype "input"))
      (node (ref "R2") (pin "1") (pinfunction "1_1") (pintype "passive"))
      (node (ref "R9") (pin "2") (pinfunction "2_2") (pintype "passive"))
    )
    (net (code "46") (name "Net-(IC4-VIN-)") (class "Default")
      (node (ref "C25") (pin "2") (pinfunction "2_2") (pintype "passive"))
      (node (ref "IC4") (pin "16") (pinfunction "VIN-_16") (pintype "input"))
      (node (ref "R24") (pin "2") (pinfunction "2_2") (pintype "passive"))
      (node (ref "R28") (pin "1") (pinfunction "1_1") (pintype "passive"))
    )
    (net (code "47") (name "Net-(IC4-VRMS)") (class "Default")
      (node (ref "IC4") (pin "10") (pinfunction "VRMS_10") (pintype "output"))
      (node (ref "R30") (pin "2") (pinfunction "2_2") (pintype "passive"))
    )
    (net (code "48") (name "Net-(IC4-~{Q})") (class "Default")
      (node (ref "IC4") (pin "13") (pinfunction "~{Q}_13") (pintype "output"))
      (node (ref "R39") (pin "2") (pinfunction "2_2") (pintype "passive"))
    )
    (net (code "49") (name "Net-(IC5-IN+)") (class "Default")
      (node (ref "C26") (pin "2") (pinfunction "2_2") (pintype "passive"))
      (node (ref "IC5") (pin "3") (pinfunction "IN+_3") (pintype "input"))
      (node (ref "R29") (pin "1") (pinfunction "1_1") (pintype "passive"))
    )
    (net (code "50") (name "Net-(IC5-IN-)") (class "Default")
      (node (ref "IC5") (pin "4") (pinfunction "IN-_4") (pintype "input"))
      (node (ref "R22") (pin "2") (pinfunction "2_2") (pintype "passive"))
      (node (ref "R31") (pin "2") (pinfunction "2_2") (pintype "passive"))
    )
    (net (code "51") (name "Net-(IC5-OUT)") (class "Default")
      (node (ref "IC5") (pin "1") (pinfunction "OUT_1") (pintype "output"))
      (node (ref "R22") (pin "1") (pinfunction "1_1") (pintype "passive"))
      (node (ref "R41") (pin "2") (pinfunction "2_2") (pintype "passive"))
      (node (ref "R42") (pin "2") (pinfunction "2_2") (pintype "passive"))
    )
    (net (code "52") (name "Net-(IC5-V+)") (class "Default")
      (node (ref "C21") (pin "2") (pinfunction "2_2") (pintype "passive"))
      (node (ref "IC5") (pin "5") (pinfunction "V+_5") (pintype "power_in"))
      (node (ref "L1") (pin "1") (pinfunction "1_1") (pintype "passive"))
    )
    (net (code "53") (name "Net-(IC6-IN+)") (class "Default")
      (node (ref "C27") (pin "2") (pinfunction "2_2") (pintype "passive"))
      (node (ref "IC6") (pin "3") (pinfunction "IN+_3") (pintype "input"))
      (node (ref "R30") (pin "1") (pinfunction "1_1") (pintype "passive"))
    )
    (net (code "54") (name "Net-(IC6-IN-)") (class "Default")
      (node (ref "IC6") (pin "4") (pinfunction "IN-_4") (pintype "input"))
      (node (ref "R23") (pin "2") (pinfunction "2_2") (pintype "passive"))
      (node (ref "R32") (pin "2") (pinfunction "2_2") (pintype "passive"))
    )
    (net (code "55") (name "Net-(IC6-OUT)") (class "Default")
      (node (ref "IC6") (pin "1") (pinfunction "OUT_1") (pintype "output"))
      (node (ref "R12") (pin "1") (pinfunction "1_1") (pintype "passive"))
      (node (ref "R17") (pin "1") (pinfunction "1_1") (pintype "passive"))
      (node (ref "R23") (pin "1") (pinfunction "1_1") (pintype "passive"))
    )
    (net (code "56") (name "Net-(IC6-V+)") (class "Default")
      (node (ref "C24") (pin "2") (pinfunction "2_2") (pintype "passive"))
      (node (ref "IC6") (pin "5") (pinfunction "V+_5") (pintype "power_in"))
      (node (ref "L4") (pin "1") (pinfunction "1_1") (pintype "passive"))
    )
    (net (code "57") (name "Net-(IC7-DXP)") (class "Default")
      (node (ref "C35") (pin "2") (pinfunction "2_2") (pintype "passive"))
      (node (ref "IC7") (pin "3") (pinfunction "DXP_3") (pintype "input"))
      (node (ref "T2") (pin "2") (pinfunction "E_2") (pintype "passive"))
    )
    (net (code "58") (name "Net-(IC7-VCC)") (class "Default")
      (node (ref "C29") (pin "2") (pinfunction "2_2") (pintype "passive"))
      (node (ref "IC7") (pin "1") (pinfunction "VCC_1") (pintype "power_in"))
      (node (ref "R33") (pin "1") (pinfunction "1_1") (pintype "passive"))
    )
    (net (code "59") (name "OUT_BIAS") (class "Default")
      (node (ref "P6") (pin "8") (pinfunction "8_8") (pintype "passive"))
      (node (ref "R1") (pin "2") (pinfunction "2_2") (pintype "passive"))
    )
    (net (code "60") (name "P3V3") (class "Default")
      (node (ref "C13") (pin "2") (pinfunction "2_2") (pintype "passive"))
      (node (ref "P6") (pin "6") (pinfunction "6_6") (pintype "passive"))
      (node (ref "R3") (pin "1") (pinfunction "1_1") (pintype "passive"))
      (node (ref "R33") (pin "2") (pinfunction "2_2") (pintype "passive"))
      (node (ref "R34") (pin "1") (pinfunction "1_1") (pintype "passive"))
      (node (ref "R35") (pin "1") (pinfunction "1_1") (pintype "passive"))
      (node (ref "R36") (pin "1") (pinfunction "1_1") (pintype "passive"))
      (node (ref "R6") (pin "1") (pinfunction "1_1") (pintype "passive"))
      (node (ref "U8") (pin "4") (pinfunction "VCC_4") (pintype "passive"))
    )
    (net (code "61") (name "P3V3A1") (class "Default")
      (node (ref "C14") (pin "2") (pinfunction "2_2") (pintype "passive"))
      (node (ref "C17") (pin "2") (pinfunction "2_2") (pintype "passive"))
      (node (ref "C8") (pin "2") (pinfunction "2_2") (pintype "passive"))
      (node (ref "IC3") (pin "5") (pinfunction "VPOS_5") (pintype "power_in"))
      (node (ref "IC3") (pin "7") (pinfunction "VPOS_7") (pintype "power_in"))
      (node (ref "IC4") (pin "5") (pinfunction "VPOS_5") (pintype "power_in"))
      (node (ref "IC4") (pin "7") (pinfunction "VPOS_7") (pintype "power_in"))
      (node (ref "L1") (pin "2") (pinfunction "2_2") (pintype "passive"))
      (node (ref "L4") (pin "2") (pinfunction "2_2") (pintype "passive"))
      (node (ref "P3") (pin "8") (pinfunction "8_8") (pintype "passive"))
      (node (ref "R18") (pin "1") (pinfunction "1_1") (pintype "passive"))
      (node (ref "R19") (pin "2") (pinfunction "2_2") (pintype "passive"))
    )
    (net (code "62") (name "VCC_PWRAMP") (class "Default")
      (node (ref "C5") (pin "2") (pinfunction "2_2") (pintype "passive"))
      (node (ref "C6") (pin "2") (pinfunction "2_2") (pintype "passive"))
      (node (ref "C7") (pin "2") (pinfunction "2_2") (pintype "passive"))
      (node (ref "L3") (pin "2") (pinfunction "2_2") (pintype "passive"))
      (node (ref "P6") (pin "2") (pinfunction "2_2") (pintype "passive"))
      (node (ref "P6") (pin "4") (pinfunction "4_4") (pintype "passive"))
    )
    (net (code "63") (name "unconnected-(D3A-A-Pad1)") (class "Default")
      (node (ref "D3") (pin "1") (pinfunction "A_1") (pintype "passive"))
    )
    (net (code "64") (name "unconnected-(IC1-NC-Pad1)") (class "Default")
      (node (ref "IC1") (pin "1") (pinfunction "NC_1") (pintype "passive"))
    )
    (net (code "65") (name "unconnected-(IC1-NC-Pad4)") (class "Default")
      (node (ref "IC1") (pin "4") (pinfunction "NC_4") (pintype "passive"))
    )
    (net (code "66") (name "unconnected-(IC1-NC-Pad5)") (class "Default")
      (node (ref "IC1") (pin "5") (pinfunction "NC_5") (pintype "power_in"))
    )
    (net (code "67") (name "unconnected-(IC1-NC-Pad8)") (class "Default")
      (node (ref "IC1") (pin "8") (pinfunction "NC_8") (pintype "power_in"))
    )
    (net (code "68") (name "unconnected-(IC3-DNC-Pad2)") (class "Default")
      (node (ref "IC3") (pin "2") (pinfunction "DNC_2") (pintype "passive+no_connect"))
    )
    (net (code "69") (name "unconnected-(IC3-DNC-Pad6)") (class "Default")
      (node (ref "IC3") (pin "6") (pinfunction "DNC_6") (pintype "passive+no_connect"))
    )
    (net (code "70") (name "unconnected-(IC3-DNC-Pad8)") (class "Default")
      (node (ref "IC3") (pin "8") (pinfunction "DNC_8") (pintype "passive+no_connect"))
    )
    (net (code "71") (name "unconnected-(IC3-VCAL-Pad3)") (class "Default")
      (node (ref "IC3") (pin "3") (pinfunction "VCAL_3") (pintype "input+no_connect"))
    )
    (net (code "72") (name "unconnected-(IC4-DNC-Pad2)") (class "Default")
      (node (ref "IC4") (pin "2") (pinfunction "DNC_2") (pintype "passive+no_connect"))
    )
    (net (code "73") (name "unconnected-(IC4-DNC-Pad6)") (class "Default")
      (node (ref "IC4") (pin "6") (pinfunction "DNC_6") (pintype "passive+no_connect"))
    )
    (net (code "74") (name "unconnected-(IC4-DNC-Pad8)") (class "Default")
      (node (ref "IC4") (pin "8") (pinfunction "DNC_8") (pintype "passive+no_connect"))
    )
    (net (code "75") (name "unconnected-(IC4-VCAL-Pad3)") (class "Default")
      (node (ref "IC4") (pin "3") (pinfunction "VCAL_3") (pintype "input+no_connect"))
    )
  )
)
